# 09_JMP.net
KiCad netlist of a schematic drawn in EAGLE
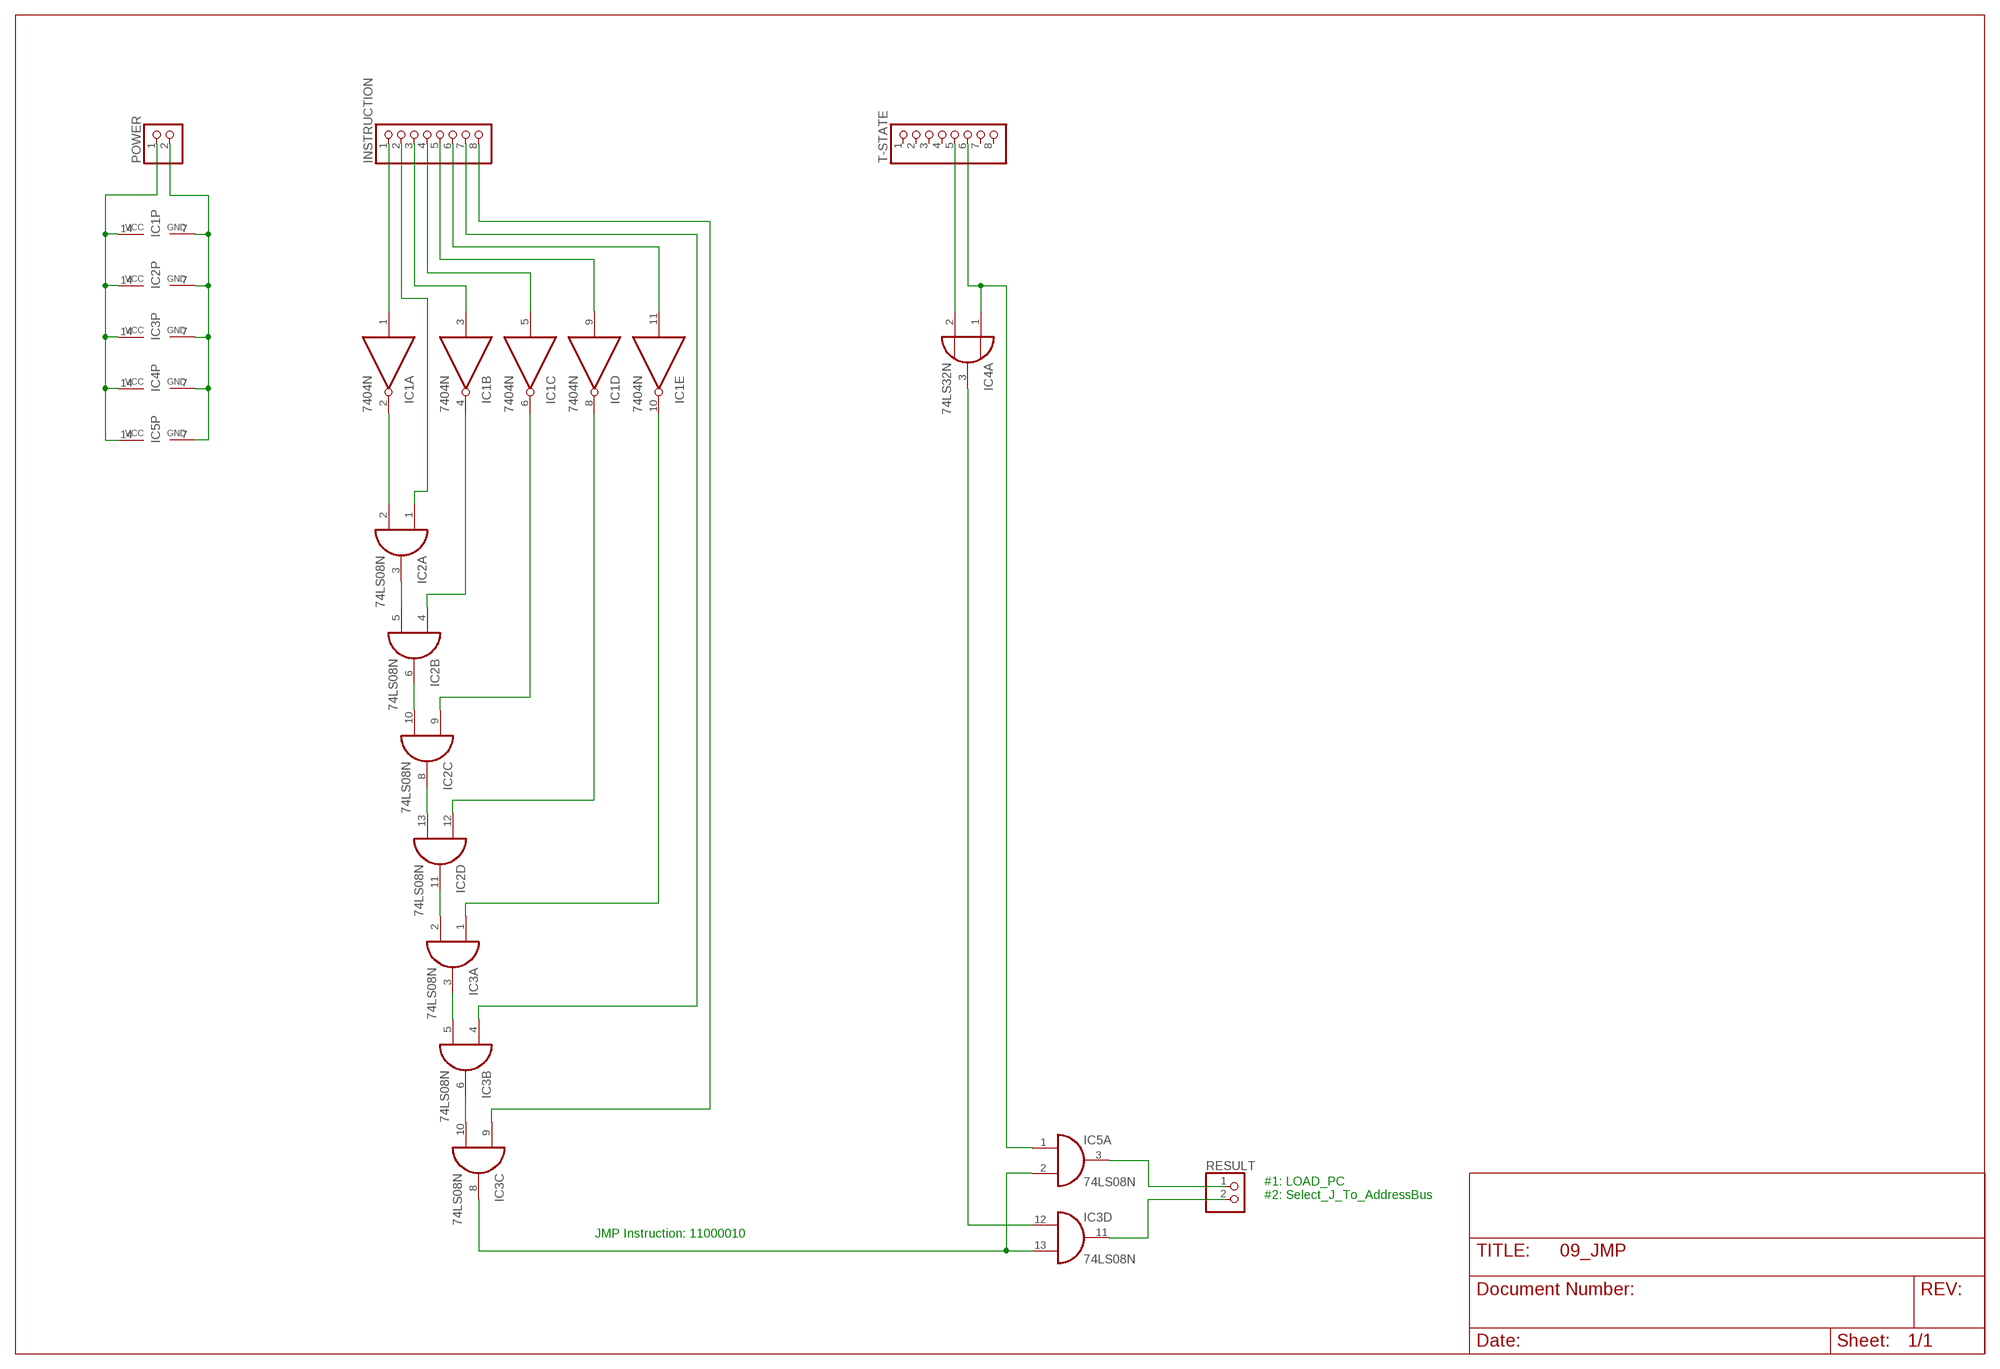
[diagram p0: schematic, sheet 1]

(export (version "E")
  (design (tool "Eeschema 10.0.6"))
  (components
    (comp (ref "IC1")
      (value "7404N")
      (footprint "eagle-import:DIL14")
      (libsource (lib "eagle-import") (part "7404N"))
    )
    (comp (ref "IC2")
      (value "74LS08N")
      (footprint "eagle-import:DIL14")
      (libsource (lib "eagle-import") (part "7408NLS"))
    )
    (comp (ref "IC3")
      (value "74LS08N")
      (footprint "eagle-import:DIL14")
      (libsource (lib "eagle-import") (part "7408NLS"))
    )
    (comp (ref "IC4")
      (value "74LS32N")
      (footprint "eagle-import:DIL14")
      (libsource (lib "eagle-import") (part "7432NLS"))
    )
    (comp (ref "IC5")
      (value "74LS08N")
      (footprint "eagle-import:DIL14")
      (libsource (lib "eagle-import") (part "7408NLS"))
    )
    (comp (ref "INSTRUCTION")
      (value "PINHD-1X8")
      (footprint "eagle-import:1X08")
      (libsource (lib "eagle-import") (part "PINHD-1X8"))
    )
    (comp (ref "POWER")
      (value "PINHD-1X2")
      (footprint "eagle-import:1X02")
      (libsource (lib "eagle-import") (part "PINHD-1X2"))
    )
    (comp (ref "RESULT")
      (value "PINHD-1X2")
      (footprint "eagle-import:1X02")
      (libsource (lib "eagle-import") (part "PINHD-1X2"))
    )
    (comp (ref "T-STATE")
      (value "PINHD-1X8")
      (footprint "eagle-import:1X08")
      (libsource (lib "eagle-import") (part "PINHD-1X8"))
    )
  )
  (nets
    (net (code "1") (name "Net-(IC1A-I)") (class "Default")
      (node (ref "IC1") (pin "1") (pinfunction "I_1") (pintype "input"))
      (node (ref "INSTRUCTION") (pin "1") (pinfunction "1_1") (pintype "passive"))
    )
    (net (code "2") (name "Net-(IC1A-O)") (class "Default")
      (node (ref "IC1") (pin "2") (pinfunction "O_2") (pintype "output"))
      (node (ref "IC2") (pin "2") (pinfunction "I1_2") (pintype "input"))
    )
    (net (code "3") (name "Net-(IC1B-I)") (class "Default")
      (node (ref "IC1") (pin "3") (pinfunction "I_3") (pintype "input"))
      (node (ref "INSTRUCTION") (pin "3") (pinfunction "3_3") (pintype "passive"))
    )
    (net (code "4") (name "Net-(IC1B-O)") (class "Default")
      (node (ref "IC1") (pin "4") (pinfunction "O_4") (pintype "output"))
      (node (ref "IC2") (pin "4") (pinfunction "I0_4") (pintype "input"))
    )
    (net (code "5") (name "Net-(IC1C-I)") (class "Default")
      (node (ref "IC1") (pin "5") (pinfunction "I_5") (pintype "input"))
      (node (ref "INSTRUCTION") (pin "4") (pinfunction "4_4") (pintype "passive"))
    )
    (net (code "6") (name "Net-(IC1C-O)") (class "Default")
      (node (ref "IC1") (pin "6") (pinfunction "O_6") (pintype "output"))
      (node (ref "IC2") (pin "9") (pinfunction "I0_9") (pintype "input"))
    )
    (net (code "7") (name "Net-(IC1D-I)") (class "Default")
      (node (ref "IC1") (pin "9") (pinfunction "I_9") (pintype "input"))
      (node (ref "INSTRUCTION") (pin "5") (pinfunction "5_5") (pintype "passive"))
    )
    (net (code "8") (name "Net-(IC1D-O)") (class "Default")
      (node (ref "IC1") (pin "8") (pinfunction "O_8") (pintype "output"))
      (node (ref "IC2") (pin "12") (pinfunction "I0_12") (pintype "input"))
    )
    (net (code "9") (name "Net-(IC1E-I)") (class "Default")
      (node (ref "IC1") (pin "11") (pinfunction "I_11") (pintype "input"))
      (node (ref "INSTRUCTION") (pin "6") (pinfunction "6_6") (pintype "passive"))
    )
    (net (code "10") (name "Net-(IC1E-O)") (class "Default")
      (node (ref "IC1") (pin "10") (pinfunction "O_10") (pintype "output"))
      (node (ref "IC3") (pin "1") (pinfunction "I0_1") (pintype "input"))
    )
    (net (code "11") (name "Net-(IC1G-GND)") (class "Default")
      (node (ref "IC1") (pin "7") (pinfunction "GND_7") (pintype "power_in"))
      (node (ref "IC2") (pin "7") (pinfunction "GND_7") (pintype "power_in"))
      (node (ref "IC3") (pin "7") (pinfunction "GND_7") (pintype "power_in"))
      (node (ref "IC4") (pin "7") (pinfunction "GND_7") (pintype "power_in"))
      (node (ref "IC5") (pin "7") (pinfunction "GND_7") (pintype "power_in"))
      (node (ref "POWER") (pin "2") (pinfunction "2_2") (pintype "passive"))
    )
    (net (code "12") (name "Net-(IC1G-VCC)") (class "Default")
      (node (ref "IC1") (pin "14") (pinfunction "VCC_14") (pintype "power_in"))
      (node (ref "IC2") (pin "14") (pinfunction "VCC_14") (pintype "power_in"))
      (node (ref "IC3") (pin "14") (pinfunction "VCC_14") (pintype "power_in"))
      (node (ref "IC4") (pin "14") (pinfunction "VCC_14") (pintype "power_in"))
      (node (ref "IC5") (pin "14") (pinfunction "VCC_14") (pintype "power_in"))
      (node (ref "POWER") (pin "1") (pinfunction "1_1") (pintype "passive"))
    )
    (net (code "13") (name "Net-(IC2A-I0)") (class "Default")
      (node (ref "IC2") (pin "1") (pinfunction "I0_1") (pintype "input"))
      (node (ref "INSTRUCTION") (pin "2") (pinfunction "2_2") (pintype "passive"))
    )
    (net (code "14") (name "Net-(IC2A-O)") (class "Default")
      (node (ref "IC2") (pin "3") (pinfunction "O_3") (pintype "output"))
      (node (ref "IC2") (pin "5") (pinfunction "I1_5") (pintype "input"))
    )
    (net (code "15") (name "Net-(IC2B-O)") (class "Default")
      (node (ref "IC2") (pin "10") (pinfunction "I1_10") (pintype "input"))
      (node (ref "IC2") (pin "6") (pinfunction "O_6") (pintype "output"))
    )
    (net (code "16") (name "Net-(IC2C-O)") (class "Default")
      (node (ref "IC2") (pin "13") (pinfunction "I1_13") (pintype "input"))
      (node (ref "IC2") (pin "8") (pinfunction "O_8") (pintype "output"))
    )
    (net (code "17") (name "Net-(IC2D-O)") (class "Default")
      (node (ref "IC2") (pin "11") (pinfunction "O_11") (pintype "output"))
      (node (ref "IC3") (pin "2") (pinfunction "I1_2") (pintype "input"))
    )
    (net (code "18") (name "Net-(IC3A-O)") (class "Default")
      (node (ref "IC3") (pin "3") (pinfunction "O_3") (pintype "output"))
      (node (ref "IC3") (pin "5") (pinfunction "I1_5") (pintype "input"))
    )
    (net (code "19") (name "Net-(IC3B-I0)") (class "Default")
      (node (ref "IC3") (pin "4") (pinfunction "I0_4") (pintype "input"))
      (node (ref "INSTRUCTION") (pin "7") (pinfunction "7_7") (pintype "passive"))
    )
    (net (code "20") (name "Net-(IC3B-O)") (class "Default")
      (node (ref "IC3") (pin "10") (pinfunction "I1_10") (pintype "input"))
      (node (ref "IC3") (pin "6") (pinfunction "O_6") (pintype "output"))
    )
    (net (code "21") (name "Net-(IC3C-I0)") (class "Default")
      (node (ref "IC3") (pin "9") (pinfunction "I0_9") (pintype "input"))
      (node (ref "INSTRUCTION") (pin "8") (pinfunction "8_8") (pintype "passive"))
    )
    (net (code "22") (name "Net-(IC3C-O)") (class "Default")
      (node (ref "IC3") (pin "13") (pinfunction "I1_13") (pintype "input"))
      (node (ref "IC3") (pin "8") (pinfunction "O_8") (pintype "output"))
      (node (ref "IC5") (pin "2") (pinfunction "I1_2") (pintype "input"))
    )
    (net (code "23") (name "Net-(IC3D-I0)") (class "Default")
      (node (ref "IC3") (pin "12") (pinfunction "I0_12") (pintype "input"))
      (node (ref "IC4") (pin "3") (pinfunction "O_3") (pintype "output"))
    )
    (net (code "24") (name "Net-(IC3D-O)") (class "Default")
      (node (ref "IC3") (pin "11") (pinfunction "O_11") (pintype "output"))
      (node (ref "RESULT") (pin "2") (pinfunction "2_2") (pintype "passive"))
    )
    (net (code "25") (name "Net-(IC4A-I0)") (class "Default")
      (node (ref "IC4") (pin "1") (pinfunction "I0_1") (pintype "input"))
      (node (ref "IC5") (pin "1") (pinfunction "I0_1") (pintype "input"))
      (node (ref "T-STATE") (pin "6") (pinfunction "6_6") (pintype "passive"))
    )
    (net (code "26") (name "Net-(IC4A-I1)") (class "Default")
      (node (ref "IC4") (pin "2") (pinfunction "I1_2") (pintype "input"))
      (node (ref "T-STATE") (pin "5") (pinfunction "5_5") (pintype "passive"))
    )
    (net (code "27") (name "Net-(IC5A-O)") (class "Default")
      (node (ref "IC5") (pin "3") (pinfunction "O_3") (pintype "output"))
      (node (ref "RESULT") (pin "1") (pinfunction "1_1") (pintype "passive"))
    )
    (net (code "28") (name "unconnected-(T-STATE-Pad1)") (class "Default")
      (node (ref "T-STATE") (pin "1") (pinfunction "1_1") (pintype "passive"))
    )
    (net (code "29") (name "unconnected-(T-STATE-Pad2)") (class "Default")
      (node (ref "T-STATE") (pin "2") (pinfunction "2_2") (pintype "passive"))
    )
    (net (code "30") (name "unconnected-(T-STATE-Pad3)") (class "Default")
      (node (ref "T-STATE") (pin "3") (pinfunction "3_3") (pintype "passive"))
    )
    (net (code "31") (name "unconnected-(T-STATE-Pad4)") (class "Default")
      (node (ref "T-STATE") (pin "4") (pinfunction "4_4") (pintype "passive"))
    )
    (net (code "32") (name "unconnected-(T-STATE-Pad7)") (class "Default")
      (node (ref "T-STATE") (pin "7") (pinfunction "7_7") (pintype "passive"))
    )
    (net (code "33") (name "unconnected-(T-STATE-Pad8)") (class "Default")
      (node (ref "T-STATE") (pin "8") (pinfunction "8_8") (pintype "passive"))
    )
  )
)
